# Relay.net
KiCad netlist of a schematic drawn in EAGLE
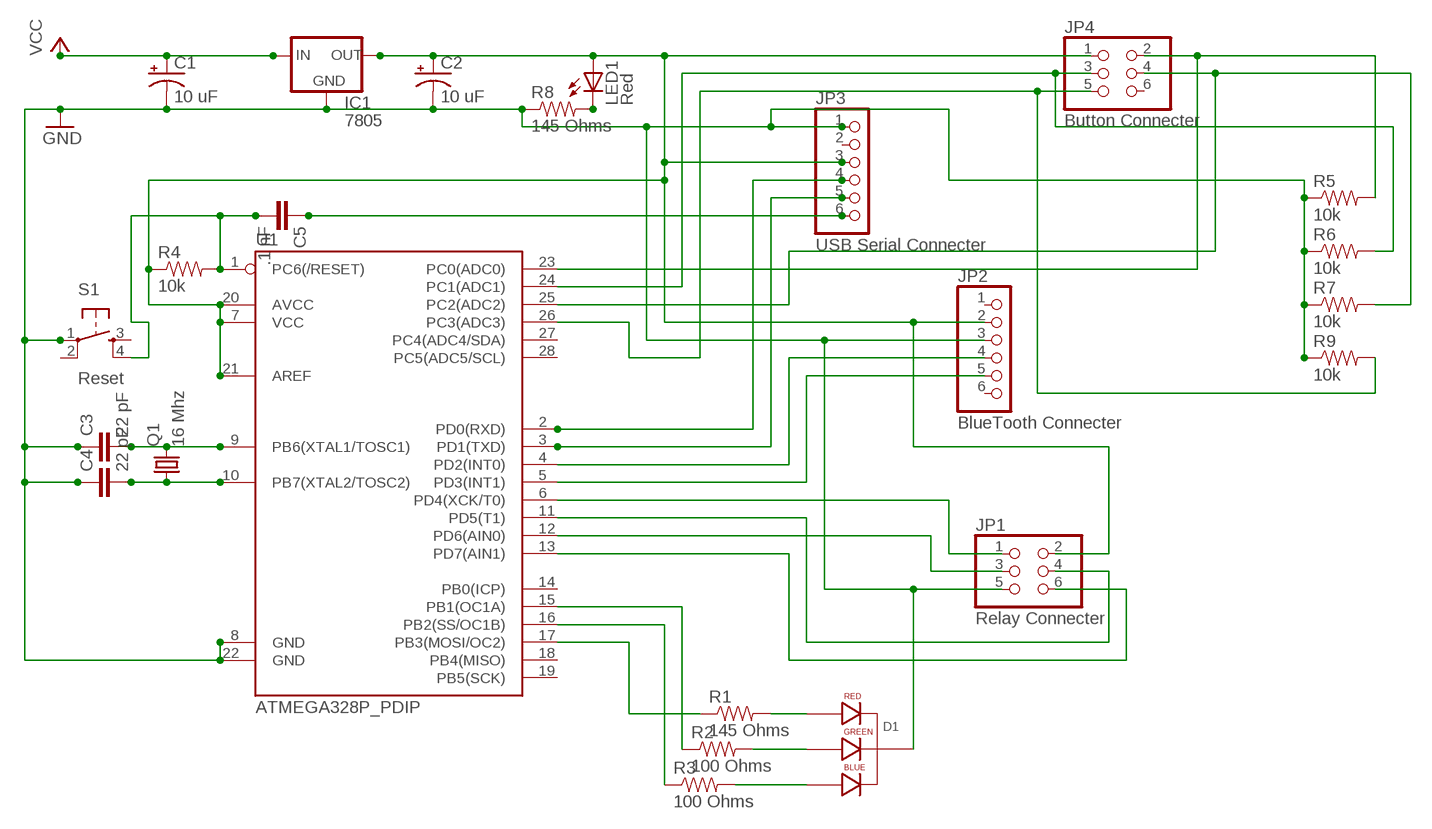
[diagram p0: schematic, sheet 1]

(export (version "E")
  (design (tool "Eeschema 10.0.6"))
  (components
    (comp (ref "C1")
      (value "10 uF")
      (footprint "eagle-import:CPOL-RADIAL-10UF-25V")
      (libsource (lib "eagle-import") (part "CAP_POLPTH2"))
    )
    (comp (ref "C2")
      (value "10 uF")
      (footprint "eagle-import:CPOL-RADIAL-10UF-25V")
      (libsource (lib "eagle-import") (part "CAP_POLPTH2"))
    )
    (comp (ref "C3")
      (value "22 pF")
      (footprint "eagle-import:CAP-PTH-SMALL2")
      (libsource (lib "eagle-import") (part "CAPPTH2"))
    )
    (comp (ref "C4")
      (value "22 pF")
      (footprint "eagle-import:CAP-PTH-SMALL2")
      (libsource (lib "eagle-import") (part "CAPPTH2"))
    )
    (comp (ref "C5")
      (value ".1 nF")
      (footprint "eagle-import:CAP-PTH-SMALL2")
      (libsource (lib "eagle-import") (part "CAPPTH2"))
    )
    (comp (ref "D1")
      (value "LED-RGB-CC-THRUCLEAR")
      (footprint "eagle-import:LED-RGB-THRU")
      (libsource (lib "eagle-import") (part "LED-RGB-CC-THRUCLEAR"))
    )
    (comp (ref "IC1")
      (value "7805")
      (footprint "eagle-import:78XXS")
      (libsource (lib "eagle-import") (part "78XXS"))
    )
    (comp (ref "JP1")
      (value "Relay Connecter")
      (footprint "eagle-import:2X03")
      (libsource (lib "eagle-import") (part "PINHD-2X3"))
    )
    (comp (ref "JP2")
      (value "BlueTooth Connecter")
      (footprint "eagle-import:1X06")
      (libsource (lib "eagle-import") (part "PINHD-1X6"))
    )
    (comp (ref "JP3")
      (value "USB Serial Connecter")
      (footprint "eagle-import:1X06")
      (libsource (lib "eagle-import") (part "PINHD-1X6"))
    )
    (comp (ref "JP4")
      (value "Button Connecter")
      (footprint "eagle-import:2X03")
      (libsource (lib "eagle-import") (part "PINHD-2X3"))
    )
    (comp (ref "LED1")
      (value "Red")
      (footprint "eagle-import:LED3MM")
      (libsource (lib "eagle-import") (part "LED3MM"))
    )
    (comp (ref "Q1")
      (value "16 Mhz")
      (footprint "eagle-import:HC49_S")
      (libsource (lib "eagle-import") (part "CRYSTALHC49S"))
    )
    (comp (ref "R1")
      (value "145 Ohms")
      (footprint "eagle-import:AXIAL-0.4")
      (libsource (lib "eagle-import") (part "RESISTORPTH-1/4W"))
    )
    (comp (ref "R2")
      (value "100 Ohms")
      (footprint "eagle-import:AXIAL-0.4")
      (libsource (lib "eagle-import") (part "RESISTORPTH-1/4W"))
    )
    (comp (ref "R3")
      (value "100 Ohms")
      (footprint "eagle-import:AXIAL-0.4")
      (libsource (lib "eagle-import") (part "RESISTORPTH-1/4W"))
    )
    (comp (ref "R4")
      (value "10k")
      (footprint "eagle-import:0402-RES")
      (libsource (lib "eagle-import") (part "10KOHM1/10W1%(0603)"))
    )
    (comp (ref "R5")
      (value "10k")
      (footprint "eagle-import:0402-RES")
      (libsource (lib "eagle-import") (part "10KOHM1/10W1%(0603)"))
    )
    (comp (ref "R6")
      (value "10k")
      (footprint "eagle-import:0402-RES")
      (libsource (lib "eagle-import") (part "10KOHM1/10W1%(0603)"))
    )
    (comp (ref "R7")
      (value "10k")
      (footprint "eagle-import:0402-RES")
      (libsource (lib "eagle-import") (part "10KOHM1/10W1%(0603)"))
    )
    (comp (ref "R8")
      (value "145 Ohms")
      (footprint "eagle-import:AXIAL-0.4")
      (libsource (lib "eagle-import") (part "RESISTORPTH-1/4W"))
    )
    (comp (ref "R9")
      (value "10k")
      (footprint "eagle-import:0402-RES")
      (libsource (lib "eagle-import") (part "10KOHM1/10W1%(0603)"))
    )
    (comp (ref "S1")
      (value "Reset")
      (footprint "eagle-import:TACTILE-PTH")
      (libsource (lib "eagle-import") (part "TAC_SWITCHPTH"))
    )
    (comp (ref "U1")
      (value "ATMEGA328P_PDIP")
      (footprint "eagle-import:DIL28-3")
      (libsource (lib "eagle-import") (part "ATMEGA328P_PDIP"))
    )
  )
  (nets
    (net (code "1") (name "GND") (class "Default")
      (node (ref "C1") (pin "2") (pinfunction "-_2") (pintype "passive"))
      (node (ref "C2") (pin "2") (pinfunction "-_2") (pintype "passive"))
      (node (ref "C3") (pin "1") (pinfunction "1_1") (pintype "passive"))
      (node (ref "C4") (pin "1") (pinfunction "1_1") (pintype "passive"))
      (node (ref "D1") (pin "2") (pinfunction "CATHODE_2") (pintype "bidirectional"))
      (node (ref "IC1") (pin "GND") (pinfunction "GND_GND") (pintype "input"))
      (node (ref "JP1") (pin "5") (pinfunction "5_5") (pintype "passive"))
      (node (ref "JP2") (pin "3") (pinfunction "3_3") (pintype "passive"))
      (node (ref "JP3") (pin "1") (pinfunction "1_1") (pintype "passive"))
      (node (ref "R5") (pin "1") (pinfunction "1_1") (pintype "passive"))
      (node (ref "R6") (pin "1") (pinfunction "1_1") (pintype "passive"))
      (node (ref "R7") (pin "1") (pinfunction "1_1") (pintype "passive"))
      (node (ref "R8") (pin "P$1") (pinfunction "1_P$1") (pintype "passive"))
      (node (ref "R9") (pin "1") (pinfunction "1_1") (pintype "passive"))
      (node (ref "S1") (pin "1") (pinfunction "1_1") (pintype "passive"))
      (node (ref "U1") (pin "22") (pinfunction "GND_22") (pintype "bidirectional"))
      (node (ref "U1") (pin "8") (pinfunction "GND_8") (pintype "bidirectional"))
    )
    (net (code "2") (name "Net-(C2-+)") (class "Default")
      (node (ref "C2") (pin "1") (pinfunction "+_1") (pintype "passive"))
      (node (ref "IC1") (pin "OUT") (pinfunction "OUT_OUT") (pintype "passive"))
      (node (ref "JP1") (pin "2") (pinfunction "2_2") (pintype "passive"))
      (node (ref "JP2") (pin "2") (pinfunction "2_2") (pintype "passive"))
      (node (ref "JP3") (pin "3") (pinfunction "3_3") (pintype "passive"))
      (node (ref "JP4") (pin "1") (pinfunction "1_1") (pintype "passive"))
      (node (ref "LED1") (pin "A") (pinfunction "A_A") (pintype "passive"))
      (node (ref "R4") (pin "1") (pinfunction "1_1") (pintype "passive"))
      (node (ref "U1") (pin "20") (pinfunction "AVCC_20") (pintype "bidirectional"))
      (node (ref "U1") (pin "21") (pinfunction "AREF_21") (pintype "bidirectional"))
      (node (ref "U1") (pin "7") (pinfunction "VCC_7") (pintype "bidirectional"))
    )
    (net (code "3") (name "Net-(C5-Pad1)") (class "Default")
      (node (ref "C5") (pin "1") (pinfunction "1_1") (pintype "passive"))
      (node (ref "JP3") (pin "6") (pinfunction "6_6") (pintype "passive"))
    )
    (net (code "4") (name "Net-(D1-BLUE_CATHODE)") (class "Default")
      (node (ref "D1") (pin "4") (pinfunction "BLUE_CATHODE_4") (pintype "bidirectional"))
      (node (ref "R3") (pin "P$2") (pinfunction "2_P$2") (pintype "passive"))
    )
    (net (code "5") (name "Net-(D1-GREEN_CATHODE)") (class "Default")
      (node (ref "D1") (pin "3") (pinfunction "GREEN_CATHODE_3") (pintype "bidirectional"))
      (node (ref "R2") (pin "P$2") (pinfunction "2_P$2") (pintype "passive"))
    )
    (net (code "6") (name "Net-(D1-RED_CATHODE)") (class "Default")
      (node (ref "D1") (pin "1") (pinfunction "RED_CATHODE_1") (pintype "bidirectional"))
      (node (ref "R1") (pin "P$2") (pinfunction "2_P$2") (pintype "passive"))
    )
    (net (code "7") (name "Net-(LED1-C)") (class "Default")
      (node (ref "LED1") (pin "K") (pinfunction "C_K") (pintype "passive"))
      (node (ref "R8") (pin "P$2") (pinfunction "2_P$2") (pintype "passive"))
    )
    (net (code "8") (name "Net-(R1-1)") (class "Default")
      (node (ref "R1") (pin "P$1") (pinfunction "1_P$1") (pintype "passive"))
      (node (ref "U1") (pin "17") (pinfunction "PB3(MOSI/OC2)_17") (pintype "bidirectional"))
    )
    (net (code "9") (name "Net-(R2-1)") (class "Default")
      (node (ref "R2") (pin "P$1") (pinfunction "1_P$1") (pintype "passive"))
      (node (ref "U1") (pin "15") (pinfunction "PB1(OC1A)_15") (pintype "bidirectional"))
    )
    (net (code "10") (name "Net-(R3-1)") (class "Default")
      (node (ref "R3") (pin "P$1") (pinfunction "1_P$1") (pintype "passive"))
      (node (ref "U1") (pin "16") (pinfunction "PB2(SS/OC1B)_16") (pintype "bidirectional"))
    )
    (net (code "11") (name "Net-(U1-PB6(XTAL1{slash}TOSC1))") (class "Default")
      (node (ref "C3") (pin "2") (pinfunction "2_2") (pintype "passive"))
      (node (ref "Q1") (pin "2") (pinfunction "2_2") (pintype "passive"))
      (node (ref "U1") (pin "9") (pinfunction "PB6(XTAL1/TOSC1)_9") (pintype "bidirectional"))
    )
    (net (code "12") (name "Net-(U1-PB7(XTAL2{slash}TOSC2))") (class "Default")
      (node (ref "C4") (pin "2") (pinfunction "2_2") (pintype "passive"))
      (node (ref "Q1") (pin "1") (pinfunction "1_1") (pintype "passive"))
      (node (ref "U1") (pin "10") (pinfunction "PB7(XTAL2/TOSC2)_10") (pintype "bidirectional"))
    )
    (net (code "13") (name "Net-(U1-PC0(ADC0))") (class "Default")
      (node (ref "JP4") (pin "2") (pinfunction "2_2") (pintype "passive"))
      (node (ref "R5") (pin "2") (pinfunction "2_2") (pintype "passive"))
      (node (ref "U1") (pin "23") (pinfunction "PC0(ADC0)_23") (pintype "bidirectional"))
    )
    (net (code "14") (name "Net-(U1-PC1(ADC1))") (class "Default")
      (node (ref "JP4") (pin "3") (pinfunction "3_3") (pintype "passive"))
      (node (ref "R6") (pin "2") (pinfunction "2_2") (pintype "passive"))
      (node (ref "U1") (pin "24") (pinfunction "PC1(ADC1)_24") (pintype "bidirectional"))
    )
    (net (code "15") (name "Net-(U1-PC2(ADC2))") (class "Default")
      (node (ref "JP4") (pin "4") (pinfunction "4_4") (pintype "passive"))
      (node (ref "R7") (pin "2") (pinfunction "2_2") (pintype "passive"))
      (node (ref "U1") (pin "25") (pinfunction "PC2(ADC2)_25") (pintype "bidirectional"))
    )
    (net (code "16") (name "Net-(U1-PC3(ADC3))") (class "Default")
      (node (ref "JP4") (pin "5") (pinfunction "5_5") (pintype "passive"))
      (node (ref "R9") (pin "2") (pinfunction "2_2") (pintype "passive"))
      (node (ref "U1") (pin "26") (pinfunction "PC3(ADC3)_26") (pintype "bidirectional"))
    )
    (net (code "17") (name "Net-(U1-PC6({slash}RESET))") (class "Default")
      (node (ref "C5") (pin "2") (pinfunction "2_2") (pintype "passive"))
      (node (ref "R4") (pin "2") (pinfunction "2_2") (pintype "passive"))
      (node (ref "S1") (pin "4") (pinfunction "4_4") (pintype "passive"))
      (node (ref "U1") (pin "1") (pinfunction "PC6(/RESET)_1") (pintype "bidirectional"))
    )
    (net (code "18") (name "Net-(U1-PD0(RXD))") (class "Default")
      (node (ref "JP3") (pin "4") (pinfunction "4_4") (pintype "passive"))
      (node (ref "U1") (pin "2") (pinfunction "PD0(RXD)_2") (pintype "bidirectional"))
    )
    (net (code "19") (name "Net-(U1-PD1(TXD))") (class "Default")
      (node (ref "JP3") (pin "5") (pinfunction "5_5") (pintype "passive"))
      (node (ref "U1") (pin "3") (pinfunction "PD1(TXD)_3") (pintype "bidirectional"))
    )
    (net (code "20") (name "Net-(U1-PD2(INT0))") (class "Default")
      (node (ref "JP2") (pin "4") (pinfunction "4_4") (pintype "passive"))
      (node (ref "U1") (pin "4") (pinfunction "PD2(INT0)_4") (pintype "bidirectional"))
    )
    (net (code "21") (name "Net-(U1-PD3(INT1))") (class "Default")
      (node (ref "JP2") (pin "5") (pinfunction "5_5") (pintype "passive"))
      (node (ref "U1") (pin "5") (pinfunction "PD3(INT1)_5") (pintype "bidirectional"))
    )
    (net (code "22") (name "Net-(U1-PD4(XCK{slash}T0))") (class "Default")
      (node (ref "JP1") (pin "1") (pinfunction "1_1") (pintype "passive"))
      (node (ref "U1") (pin "6") (pinfunction "PD4(XCK/T0)_6") (pintype "bidirectional"))
    )
    (net (code "23") (name "Net-(U1-PD5(T1))") (class "Default")
      (node (ref "JP1") (pin "4") (pinfunction "4_4") (pintype "passive"))
      (node (ref "U1") (pin "11") (pinfunction "PD5(T1)_11") (pintype "bidirectional"))
    )
    (net (code "24") (name "Net-(U1-PD6(AIN0))") (class "Default")
      (node (ref "JP1") (pin "3") (pinfunction "3_3") (pintype "passive"))
      (node (ref "U1") (pin "12") (pinfunction "PD6(AIN0)_12") (pintype "bidirectional"))
    )
    (net (code "25") (name "Net-(U1-PD7(AIN1))") (class "Default")
      (node (ref "JP1") (pin "6") (pinfunction "6_6") (pintype "passive"))
      (node (ref "U1") (pin "13") (pinfunction "PD7(AIN1)_13") (pintype "bidirectional"))
    )
    (net (code "26") (name "VCC") (class "Default")
      (node (ref "C1") (pin "1") (pinfunction "+_1") (pintype "passive"))
      (node (ref "IC1") (pin "IN") (pinfunction "IN_IN") (pintype "input"))
    )
    (net (code "27") (name "unconnected-(JP2-Pad1)") (class "Default")
      (node (ref "JP2") (pin "1") (pinfunction "1_1") (pintype "passive"))
    )
    (net (code "28") (name "unconnected-(JP2-Pad6)") (class "Default")
      (node (ref "JP2") (pin "6") (pinfunction "6_6") (pintype "passive"))
    )
    (net (code "29") (name "unconnected-(JP3-Pad2)") (class "Default")
      (node (ref "JP3") (pin "2") (pinfunction "2_2") (pintype "passive"))
    )
    (net (code "30") (name "unconnected-(JP4-Pad6)") (class "Default")
      (node (ref "JP4") (pin "6") (pinfunction "6_6") (pintype "passive"))
    )
    (net (code "31") (name "unconnected-(S1-Pad2)") (class "Default")
      (node (ref "S1") (pin "2") (pinfunction "2_2") (pintype "passive"))
    )
    (net (code "32") (name "unconnected-(S1-Pad3)") (class "Default")
      (node (ref "S1") (pin "3") (pinfunction "3_3") (pintype "passive"))
    )
    (net (code "33") (name "unconnected-(U1-PB0(ICP)-Pad14)") (class "Default")
      (node (ref "U1") (pin "14") (pinfunction "PB0(ICP)_14") (pintype "bidirectional"))
    )
    (net (code "34") (name "unconnected-(U1-PB4(MISO)-Pad18)") (class "Default")
      (node (ref "U1") (pin "18") (pinfunction "PB4(MISO)_18") (pintype "bidirectional"))
    )
    (net (code "35") (name "unconnected-(U1-PB5(SCK)-Pad19)") (class "Default")
      (node (ref "U1") (pin "19") (pinfunction "PB5(SCK)_19") (pintype "bidirectional"))
    )
    (net (code "36") (name "unconnected-(U1-PC4(ADC4{slash}SDA)-Pad27)") (class "Default")
      (node (ref "U1") (pin "27") (pinfunction "PC4(ADC4/SDA)_27") (pintype "bidirectional"))
    )
    (net (code "37") (name "unconnected-(U1-PC5(ADC5{slash}SCL)-Pad28)") (class "Default")
      (node (ref "U1") (pin "28") (pinfunction "PC5(ADC5/SCL)_28") (pintype "bidirectional"))
    )
  )
)
